# matrix-2col.net
KiCad netlist of a schematic drawn in EAGLE
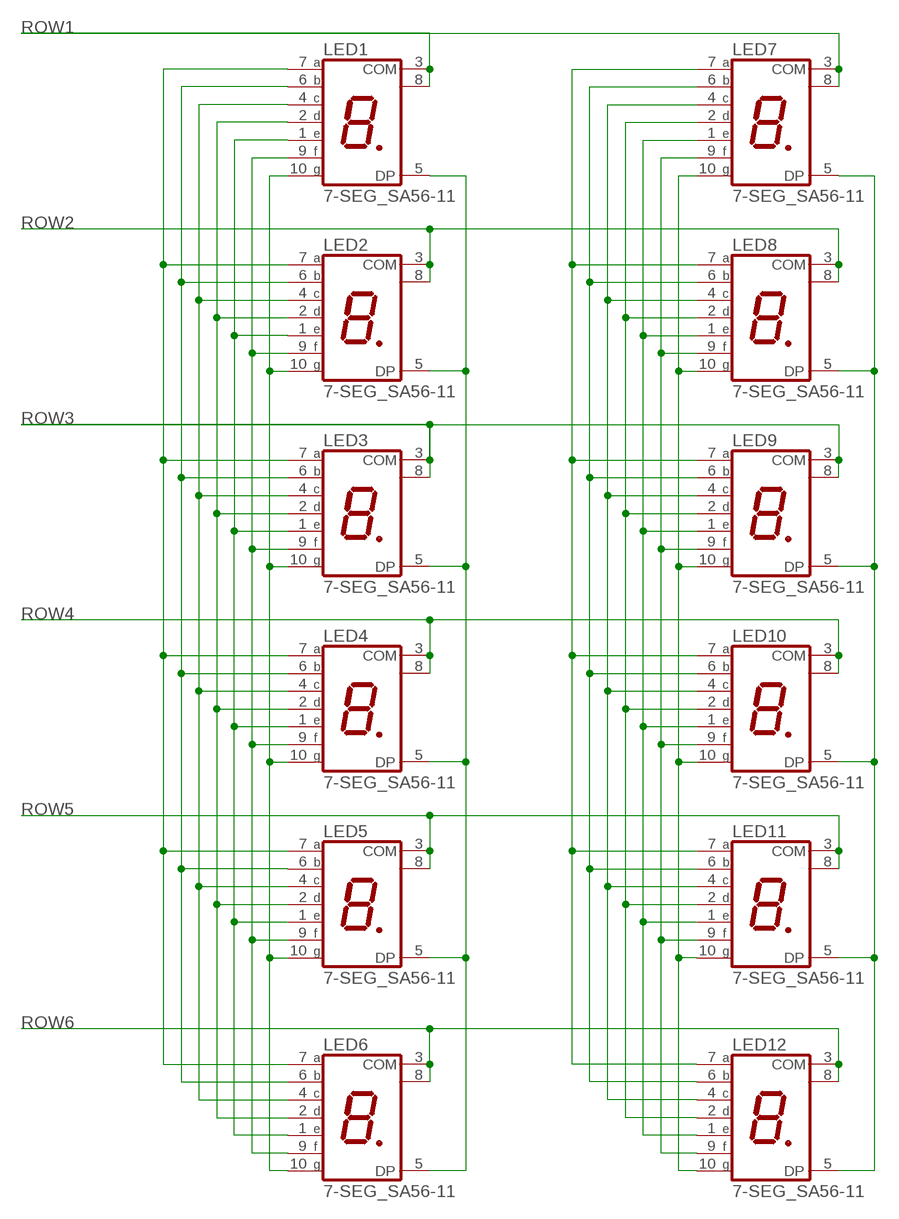
[diagram p0: schematic, sheet 1]

(export (version "E")
  (design (tool "Eeschema 10.0.6"))
  (components
    (comp (ref "LED1")
      (value "7-SEG_SA56-11")
      (footprint "eagle-import:SA56-11")
      (libsource (lib "eagle-import") (part "7-SEG_SA56-11"))
    )
    (comp (ref "LED2")
      (value "7-SEG_SA56-11")
      (footprint "eagle-import:SA56-11")
      (libsource (lib "eagle-import") (part "7-SEG_SA56-11"))
    )
    (comp (ref "LED3")
      (value "7-SEG_SA56-11")
      (footprint "eagle-import:SA56-11")
      (libsource (lib "eagle-import") (part "7-SEG_SA56-11"))
    )
    (comp (ref "LED4")
      (value "7-SEG_SA56-11")
      (footprint "eagle-import:SA56-11")
      (libsource (lib "eagle-import") (part "7-SEG_SA56-11"))
    )
    (comp (ref "LED5")
      (value "7-SEG_SA56-11")
      (footprint "eagle-import:SA56-11")
      (libsource (lib "eagle-import") (part "7-SEG_SA56-11"))
    )
    (comp (ref "LED6")
      (value "7-SEG_SA56-11")
      (footprint "eagle-import:SA56-11")
      (libsource (lib "eagle-import") (part "7-SEG_SA56-11"))
    )
    (comp (ref "LED7")
      (value "7-SEG_SA56-11")
      (footprint "eagle-import:SA56-11")
      (libsource (lib "eagle-import") (part "7-SEG_SA56-11"))
    )
    (comp (ref "LED8")
      (value "7-SEG_SA56-11")
      (footprint "eagle-import:SA56-11")
      (libsource (lib "eagle-import") (part "7-SEG_SA56-11"))
    )
    (comp (ref "LED9")
      (value "7-SEG_SA56-11")
      (footprint "eagle-import:SA56-11")
      (libsource (lib "eagle-import") (part "7-SEG_SA56-11"))
    )
    (comp (ref "LED10")
      (value "7-SEG_SA56-11")
      (footprint "eagle-import:SA56-11")
      (libsource (lib "eagle-import") (part "7-SEG_SA56-11"))
    )
    (comp (ref "LED11")
      (value "7-SEG_SA56-11")
      (footprint "eagle-import:SA56-11")
      (libsource (lib "eagle-import") (part "7-SEG_SA56-11"))
    )
    (comp (ref "LED12")
      (value "7-SEG_SA56-11")
      (footprint "eagle-import:SA56-11")
      (libsource (lib "eagle-import") (part "7-SEG_SA56-11"))
    )
  )
  (nets
    (net (code "1") (name "/ROW1") (class "Default")
      (node (ref "LED1") (pin "3") (pinfunction "COM_3") (pintype "passive"))
      (node (ref "LED1") (pin "8") (pinfunction "COM_8") (pintype "passive"))
      (node (ref "LED7") (pin "3") (pinfunction "COM_3") (pintype "passive"))
      (node (ref "LED7") (pin "8") (pinfunction "COM_8") (pintype "passive"))
    )
    (net (code "2") (name "/ROW2") (class "Default")
      (node (ref "LED2") (pin "3") (pinfunction "COM_3") (pintype "passive"))
      (node (ref "LED2") (pin "8") (pinfunction "COM_8") (pintype "passive"))
      (node (ref "LED8") (pin "3") (pinfunction "COM_3") (pintype "passive"))
      (node (ref "LED8") (pin "8") (pinfunction "COM_8") (pintype "passive"))
    )
    (net (code "3") (name "/ROW3") (class "Default")
      (node (ref "LED3") (pin "3") (pinfunction "COM_3") (pintype "passive"))
      (node (ref "LED3") (pin "8") (pinfunction "COM_8") (pintype "passive"))
      (node (ref "LED9") (pin "3") (pinfunction "COM_3") (pintype "passive"))
      (node (ref "LED9") (pin "8") (pinfunction "COM_8") (pintype "passive"))
    )
    (net (code "4") (name "/ROW4") (class "Default")
      (node (ref "LED10") (pin "3") (pinfunction "COM_3") (pintype "passive"))
      (node (ref "LED10") (pin "8") (pinfunction "COM_8") (pintype "passive"))
      (node (ref "LED4") (pin "3") (pinfunction "COM_3") (pintype "passive"))
      (node (ref "LED4") (pin "8") (pinfunction "COM_8") (pintype "passive"))
    )
    (net (code "5") (name "/ROW5") (class "Default")
      (node (ref "LED11") (pin "3") (pinfunction "COM_3") (pintype "passive"))
      (node (ref "LED11") (pin "8") (pinfunction "COM_8") (pintype "passive"))
      (node (ref "LED5") (pin "3") (pinfunction "COM_3") (pintype "passive"))
      (node (ref "LED5") (pin "8") (pinfunction "COM_8") (pintype "passive"))
    )
    (net (code "6") (name "/ROW6") (class "Default")
      (node (ref "LED12") (pin "3") (pinfunction "COM_3") (pintype "passive"))
      (node (ref "LED12") (pin "8") (pinfunction "COM_8") (pintype "passive"))
      (node (ref "LED6") (pin "3") (pinfunction "COM_3") (pintype "passive"))
      (node (ref "LED6") (pin "8") (pinfunction "COM_8") (pintype "passive"))
    )
    (net (code "7") (name "Net-(LED1-A)") (class "Default")
      (node (ref "LED1") (pin "7") (pinfunction "A_7") (pintype "passive"))
      (node (ref "LED2") (pin "7") (pinfunction "A_7") (pintype "passive"))
      (node (ref "LED3") (pin "7") (pinfunction "A_7") (pintype "passive"))
      (node (ref "LED4") (pin "7") (pinfunction "A_7") (pintype "passive"))
      (node (ref "LED5") (pin "7") (pinfunction "A_7") (pintype "passive"))
      (node (ref "LED6") (pin "7") (pinfunction "A_7") (pintype "passive"))
    )
    (net (code "8") (name "Net-(LED1-B)") (class "Default")
      (node (ref "LED1") (pin "6") (pinfunction "B_6") (pintype "passive"))
      (node (ref "LED2") (pin "6") (pinfunction "B_6") (pintype "passive"))
      (node (ref "LED3") (pin "6") (pinfunction "B_6") (pintype "passive"))
      (node (ref "LED4") (pin "6") (pinfunction "B_6") (pintype "passive"))
      (node (ref "LED5") (pin "6") (pinfunction "B_6") (pintype "passive"))
      (node (ref "LED6") (pin "6") (pinfunction "B_6") (pintype "passive"))
    )
    (net (code "9") (name "Net-(LED1-C)") (class "Default")
      (node (ref "LED1") (pin "4") (pinfunction "C_4") (pintype "passive"))
      (node (ref "LED2") (pin "4") (pinfunction "C_4") (pintype "passive"))
      (node (ref "LED3") (pin "4") (pinfunction "C_4") (pintype "passive"))
      (node (ref "LED4") (pin "4") (pinfunction "C_4") (pintype "passive"))
      (node (ref "LED5") (pin "4") (pinfunction "C_4") (pintype "passive"))
      (node (ref "LED6") (pin "4") (pinfunction "C_4") (pintype "passive"))
    )
    (net (code "10") (name "Net-(LED1-D)") (class "Default")
      (node (ref "LED1") (pin "2") (pinfunction "D_2") (pintype "passive"))
      (node (ref "LED2") (pin "2") (pinfunction "D_2") (pintype "passive"))
      (node (ref "LED3") (pin "2") (pinfunction "D_2") (pintype "passive"))
      (node (ref "LED4") (pin "2") (pinfunction "D_2") (pintype "passive"))
      (node (ref "LED5") (pin "2") (pinfunction "D_2") (pintype "passive"))
      (node (ref "LED6") (pin "2") (pinfunction "D_2") (pintype "passive"))
    )
    (net (code "11") (name "Net-(LED1-DP)") (class "Default")
      (node (ref "LED1") (pin "5") (pinfunction "DP_5") (pintype "passive"))
      (node (ref "LED2") (pin "5") (pinfunction "DP_5") (pintype "passive"))
      (node (ref "LED3") (pin "5") (pinfunction "DP_5") (pintype "passive"))
      (node (ref "LED4") (pin "5") (pinfunction "DP_5") (pintype "passive"))
      (node (ref "LED5") (pin "5") (pinfunction "DP_5") (pintype "passive"))
      (node (ref "LED6") (pin "5") (pinfunction "DP_5") (pintype "passive"))
    )
    (net (code "12") (name "Net-(LED1-E)") (class "Default")
      (node (ref "LED1") (pin "1") (pinfunction "E_1") (pintype "passive"))
      (node (ref "LED2") (pin "1") (pinfunction "E_1") (pintype "passive"))
      (node (ref "LED3") (pin "1") (pinfunction "E_1") (pintype "passive"))
      (node (ref "LED4") (pin "1") (pinfunction "E_1") (pintype "passive"))
      (node (ref "LED5") (pin "1") (pinfunction "E_1") (pintype "passive"))
      (node (ref "LED6") (pin "1") (pinfunction "E_1") (pintype "passive"))
    )
    (net (code "13") (name "Net-(LED1-F)") (class "Default")
      (node (ref "LED1") (pin "9") (pinfunction "F_9") (pintype "passive"))
      (node (ref "LED2") (pin "9") (pinfunction "F_9") (pintype "passive"))
      (node (ref "LED3") (pin "9") (pinfunction "F_9") (pintype "passive"))
      (node (ref "LED4") (pin "9") (pinfunction "F_9") (pintype "passive"))
      (node (ref "LED5") (pin "9") (pinfunction "F_9") (pintype "passive"))
      (node (ref "LED6") (pin "9") (pinfunction "F_9") (pintype "passive"))
    )
    (net (code "14") (name "Net-(LED1-G)") (class "Default")
      (node (ref "LED1") (pin "10") (pinfunction "G_10") (pintype "passive"))
      (node (ref "LED2") (pin "10") (pinfunction "G_10") (pintype "passive"))
      (node (ref "LED3") (pin "10") (pinfunction "G_10") (pintype "passive"))
      (node (ref "LED4") (pin "10") (pinfunction "G_10") (pintype "passive"))
      (node (ref "LED5") (pin "10") (pinfunction "G_10") (pintype "passive"))
      (node (ref "LED6") (pin "10") (pinfunction "G_10") (pintype "passive"))
    )
    (net (code "15") (name "Net-(LED10-A)") (class "Default")
      (node (ref "LED10") (pin "7") (pinfunction "A_7") (pintype "passive"))
      (node (ref "LED11") (pin "7") (pinfunction "A_7") (pintype "passive"))
      (node (ref "LED12") (pin "7") (pinfunction "A_7") (pintype "passive"))
      (node (ref "LED7") (pin "7") (pinfunction "A_7") (pintype "passive"))
      (node (ref "LED8") (pin "7") (pinfunction "A_7") (pintype "passive"))
      (node (ref "LED9") (pin "7") (pinfunction "A_7") (pintype "passive"))
    )
    (net (code "16") (name "Net-(LED10-B)") (class "Default")
      (node (ref "LED10") (pin "6") (pinfunction "B_6") (pintype "passive"))
      (node (ref "LED11") (pin "6") (pinfunction "B_6") (pintype "passive"))
      (node (ref "LED12") (pin "6") (pinfunction "B_6") (pintype "passive"))
      (node (ref "LED7") (pin "6") (pinfunction "B_6") (pintype "passive"))
      (node (ref "LED8") (pin "6") (pinfunction "B_6") (pintype "passive"))
      (node (ref "LED9") (pin "6") (pinfunction "B_6") (pintype "passive"))
    )
    (net (code "17") (name "Net-(LED10-C)") (class "Default")
      (node (ref "LED10") (pin "4") (pinfunction "C_4") (pintype "passive"))
      (node (ref "LED11") (pin "4") (pinfunction "C_4") (pintype "passive"))
      (node (ref "LED12") (pin "4") (pinfunction "C_4") (pintype "passive"))
      (node (ref "LED7") (pin "4") (pinfunction "C_4") (pintype "passive"))
      (node (ref "LED8") (pin "4") (pinfunction "C_4") (pintype "passive"))
      (node (ref "LED9") (pin "4") (pinfunction "C_4") (pintype "passive"))
    )
    (net (code "18") (name "Net-(LED10-D)") (class "Default")
      (node (ref "LED10") (pin "2") (pinfunction "D_2") (pintype "passive"))
      (node (ref "LED11") (pin "2") (pinfunction "D_2") (pintype "passive"))
      (node (ref "LED12") (pin "2") (pinfunction "D_2") (pintype "passive"))
      (node (ref "LED7") (pin "2") (pinfunction "D_2") (pintype "passive"))
      (node (ref "LED8") (pin "2") (pinfunction "D_2") (pintype "passive"))
      (node (ref "LED9") (pin "2") (pinfunction "D_2") (pintype "passive"))
    )
    (net (code "19") (name "Net-(LED10-DP)") (class "Default")
      (node (ref "LED10") (pin "5") (pinfunction "DP_5") (pintype "passive"))
      (node (ref "LED11") (pin "5") (pinfunction "DP_5") (pintype "passive"))
      (node (ref "LED12") (pin "5") (pinfunction "DP_5") (pintype "passive"))
      (node (ref "LED7") (pin "5") (pinfunction "DP_5") (pintype "passive"))
      (node (ref "LED8") (pin "5") (pinfunction "DP_5") (pintype "passive"))
      (node (ref "LED9") (pin "5") (pinfunction "DP_5") (pintype "passive"))
    )
    (net (code "20") (name "Net-(LED10-E)") (class "Default")
      (node (ref "LED10") (pin "1") (pinfunction "E_1") (pintype "passive"))
      (node (ref "LED11") (pin "1") (pinfunction "E_1") (pintype "passive"))
      (node (ref "LED12") (pin "1") (pinfunction "E_1") (pintype "passive"))
      (node (ref "LED7") (pin "1") (pinfunction "E_1") (pintype "passive"))
      (node (ref "LED8") (pin "1") (pinfunction "E_1") (pintype "passive"))
      (node (ref "LED9") (pin "1") (pinfunction "E_1") (pintype "passive"))
    )
    (net (code "21") (name "Net-(LED10-F)") (class "Default")
      (node (ref "LED10") (pin "9") (pinfunction "F_9") (pintype "passive"))
      (node (ref "LED11") (pin "9") (pinfunction "F_9") (pintype "passive"))
      (node (ref "LED12") (pin "9") (pinfunction "F_9") (pintype "passive"))
      (node (ref "LED7") (pin "9") (pinfunction "F_9") (pintype "passive"))
      (node (ref "LED8") (pin "9") (pinfunction "F_9") (pintype "passive"))
      (node (ref "LED9") (pin "9") (pinfunction "F_9") (pintype "passive"))
    )
    (net (code "22") (name "Net-(LED10-G)") (class "Default")
      (node (ref "LED10") (pin "10") (pinfunction "G_10") (pintype "passive"))
      (node (ref "LED11") (pin "10") (pinfunction "G_10") (pintype "passive"))
      (node (ref "LED12") (pin "10") (pinfunction "G_10") (pintype "passive"))
      (node (ref "LED7") (pin "10") (pinfunction "G_10") (pintype "passive"))
      (node (ref "LED8") (pin "10") (pinfunction "G_10") (pintype "passive"))
      (node (ref "LED9") (pin "10") (pinfunction "G_10") (pintype "passive"))
    )
  )
)
